# breakout.net
KiCad netlist of a schematic drawn in EAGLE
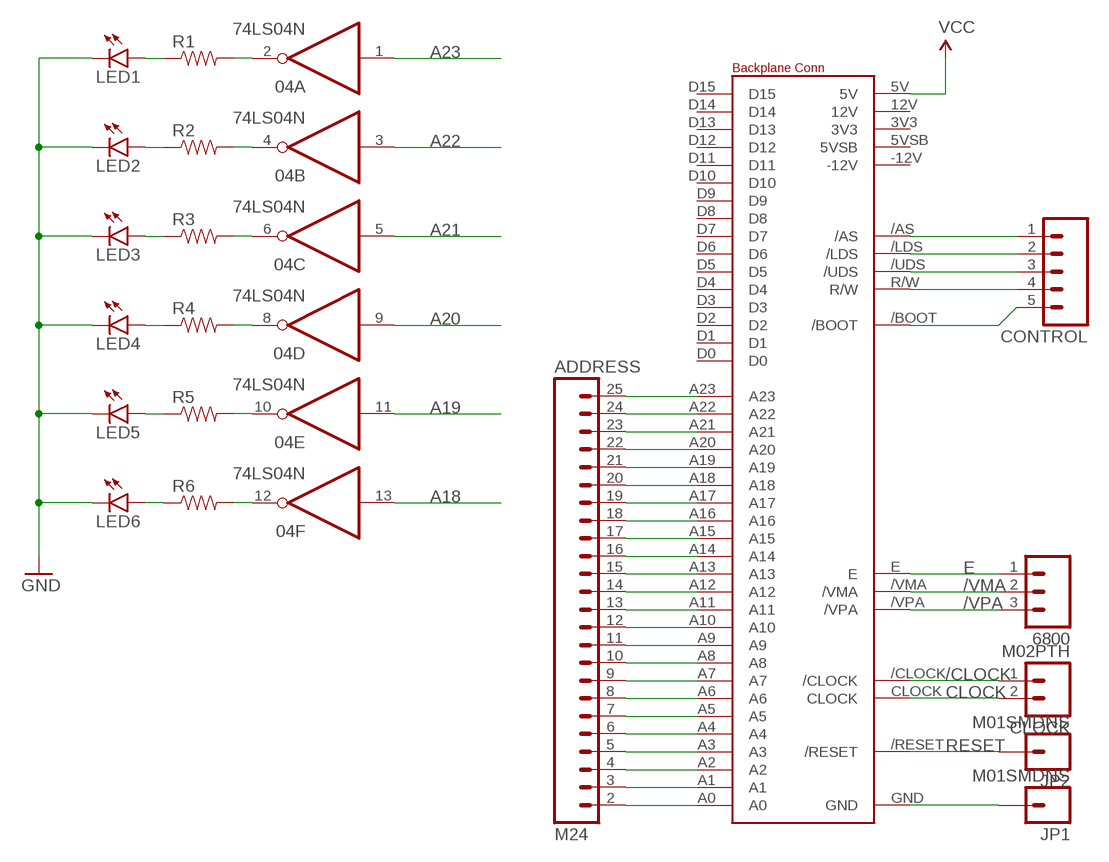
[diagram p0: schematic, sheet 1]

(export (version "E")
  (design (tool "Eeschema 10.0.6"))
  (components
    (comp (ref "04")
      (value "74LS04N")
      (footprint "eagle-import:DIL14")
      (libsource (lib "eagle-import") (part "7404NLS"))
    )
    (comp (ref "6800")
      (value "M03PTH")
      (footprint "eagle-import:1X03")
      (libsource (lib "eagle-import") (part "M03PTH"))
    )
    (comp (ref "ADDRESS")
      (value "M24")
      (footprint "eagle-import:1X24")
      (libsource (lib "eagle-import") (part "M24"))
    )
    (comp (ref "CLOCK")
      (value "M02PTH")
      (footprint "eagle-import:1X02")
      (libsource (lib "eagle-import") (part "M02PTH"))
    )
    (comp (ref "CONTROL")
      (value "M05PTH")
      (footprint "eagle-import:1X05")
      (libsource (lib "eagle-import") (part "M05PTH"))
    )
    (comp (ref "JP1")
      (value "M01SMDNS")
      (footprint "eagle-import:1X01NS")
      (libsource (lib "eagle-import") (part "M01SMDNS"))
    )
    (comp (ref "JP2")
      (value "M01SMDNS")
      (footprint "eagle-import:1X01NS")
      (libsource (lib "eagle-import") (part "M01SMDNS"))
    )
    (comp (ref "LED1")
      (value "LED1206")
      (footprint "eagle-import:LED-1206")
      (libsource (lib "eagle-import") (part "LED1206"))
    )
    (comp (ref "LED2")
      (value "LED1206")
      (footprint "eagle-import:LED-1206")
      (libsource (lib "eagle-import") (part "LED1206"))
    )
    (comp (ref "LED3")
      (value "LED1206")
      (footprint "eagle-import:LED-1206")
      (libsource (lib "eagle-import") (part "LED1206"))
    )
    (comp (ref "LED4")
      (value "LED1206")
      (footprint "eagle-import:LED-1206")
      (libsource (lib "eagle-import") (part "LED1206"))
    )
    (comp (ref "LED5")
      (value "LED1206")
      (footprint "eagle-import:LED-1206")
      (libsource (lib "eagle-import") (part "LED1206"))
    )
    (comp (ref "LED6")
      (value "LED1206")
      (footprint "eagle-import:LED-1206")
      (libsource (lib "eagle-import") (part "LED1206"))
    )
    (comp (ref "R1")
      (value "RESISTOR0603-RES")
      (footprint "eagle-import:0603-RES")
      (libsource (lib "eagle-import") (part "RESISTOR0603-RES"))
    )
    (comp (ref "R2")
      (value "RESISTOR0603-RES")
      (footprint "eagle-import:0603-RES")
      (libsource (lib "eagle-import") (part "RESISTOR0603-RES"))
    )
    (comp (ref "R3")
      (value "RESISTOR0603-RES")
      (footprint "eagle-import:0603-RES")
      (libsource (lib "eagle-import") (part "RESISTOR0603-RES"))
    )
    (comp (ref "R4")
      (value "RESISTOR0603-RES")
      (footprint "eagle-import:0603-RES")
      (libsource (lib "eagle-import") (part "RESISTOR0603-RES"))
    )
    (comp (ref "R5")
      (value "RESISTOR0603-RES")
      (footprint "eagle-import:0603-RES")
      (libsource (lib "eagle-import") (part "RESISTOR0603-RES"))
    )
    (comp (ref "R6")
      (value "RESISTOR0603-RES")
      (footprint "eagle-import:0603-RES")
      (libsource (lib "eagle-import") (part "RESISTOR0603-RES"))
    )
    (comp (ref "U$1")
      (value "BACKPLANENOHOLES")
      (footprint "eagle-import:41612-C")
      (libsource (lib "eagle-import") (part "BACKPLANENOHOLES"))
    )
  )
  (nets
    (net (code "1") (name "/A18") (class "Default")
      (node (ref "04") (pin "13") (pinfunction "I_13") (pintype "input"))
      (node (ref "ADDRESS") (pin "20") (pinfunction "20_20") (pintype "passive"))
      (node (ref "U$1") (pin "A18") (pinfunction "A18_A18") (pintype "bidirectional"))
    )
    (net (code "2") (name "/A19") (class "Default")
      (node (ref "04") (pin "11") (pinfunction "I_11") (pintype "input"))
      (node (ref "ADDRESS") (pin "21") (pinfunction "21_21") (pintype "passive"))
      (node (ref "U$1") (pin "A19") (pinfunction "A19_A19") (pintype "bidirectional"))
    )
    (net (code "3") (name "/A20") (class "Default")
      (node (ref "04") (pin "9") (pinfunction "I_9") (pintype "input"))
      (node (ref "ADDRESS") (pin "22") (pinfunction "22_22") (pintype "passive"))
      (node (ref "U$1") (pin "A20") (pinfunction "A20_A20") (pintype "bidirectional"))
    )
    (net (code "4") (name "/A21") (class "Default")
      (node (ref "04") (pin "5") (pinfunction "I_5") (pintype "input"))
      (node (ref "ADDRESS") (pin "23") (pinfunction "23_23") (pintype "passive"))
      (node (ref "U$1") (pin "A21") (pinfunction "A21_A21") (pintype "bidirectional"))
    )
    (net (code "5") (name "/A22") (class "Default")
      (node (ref "04") (pin "3") (pinfunction "I_3") (pintype "input"))
      (node (ref "ADDRESS") (pin "24") (pinfunction "24_24") (pintype "passive"))
      (node (ref "U$1") (pin "A22") (pinfunction "A22_A22") (pintype "bidirectional"))
    )
    (net (code "6") (name "/A23") (class "Default")
      (node (ref "04") (pin "1") (pinfunction "I_1") (pintype "input"))
      (node (ref "ADDRESS") (pin "25") (pinfunction "25_25") (pintype "passive"))
      (node (ref "U$1") (pin "A23") (pinfunction "A23_A23") (pintype "bidirectional"))
    )
    (net (code "7") (name "/CLOCK") (class "Default")
      (node (ref "CLOCK") (pin "2") (pinfunction "2_2") (pintype "passive"))
      (node (ref "U$1") (pin "CLOCK") (pinfunction "CLOCK_CLOCK") (pintype "bidirectional"))
    )
    (net (code "8") (name "/E") (class "Default")
      (node (ref "6800") (pin "1") (pinfunction "1_1") (pintype "passive"))
      (node (ref "U$1") (pin "E") (pinfunction "E_E") (pintype "bidirectional"))
    )
    (net (code "9") (name "/RESET") (class "Default")
      (node (ref "JP2") (pin "1") (pinfunction "1_1") (pintype "passive"))
      (node (ref "U$1") (pin "/RESET") (pinfunction "/RESET_/RESET") (pintype "bidirectional"))
    )
    (net (code "10") (name "/{slash}CLOCK") (class "Default")
      (node (ref "CLOCK") (pin "1") (pinfunction "1_1") (pintype "passive"))
      (node (ref "U$1") (pin "/CLOCK") (pinfunction "/CLOCK_/CLOCK") (pintype "bidirectional"))
    )
    (net (code "11") (name "/{slash}VMA") (class "Default")
      (node (ref "6800") (pin "2") (pinfunction "2_2") (pintype "passive"))
      (node (ref "U$1") (pin "/VMA") (pinfunction "/VMA_/VMA") (pintype "bidirectional"))
    )
    (net (code "12") (name "/{slash}VPA") (class "Default")
      (node (ref "6800") (pin "3") (pinfunction "3_3") (pintype "passive"))
      (node (ref "U$1") (pin "/VPA") (pinfunction "/VPA_/VPA") (pintype "bidirectional"))
    )
    (net (code "13") (name "GND") (class "Default")
      (node (ref "JP1") (pin "1") (pinfunction "1_1") (pintype "passive"))
      (node (ref "LED1") (pin "C") (pinfunction "C_C") (pintype "passive"))
      (node (ref "LED2") (pin "C") (pinfunction "C_C") (pintype "passive"))
      (node (ref "LED3") (pin "C") (pinfunction "C_C") (pintype "passive"))
      (node (ref "LED4") (pin "C") (pinfunction "C_C") (pintype "passive"))
      (node (ref "LED5") (pin "C") (pinfunction "C_C") (pintype "passive"))
      (node (ref "LED6") (pin "C") (pinfunction "C_C") (pintype "passive"))
      (node (ref "U$1") (pin "GND") (pinfunction "GND_GND") (pintype "bidirectional"))
    )
    (net (code "14") (name "Net-(04A-O)") (class "Default")
      (node (ref "04") (pin "2") (pinfunction "O_2") (pintype "output"))
      (node (ref "R1") (pin "2") (pinfunction "2_2") (pintype "passive"))
    )
    (net (code "15") (name "Net-(04B-O)") (class "Default")
      (node (ref "04") (pin "4") (pinfunction "O_4") (pintype "output"))
      (node (ref "R2") (pin "2") (pinfunction "2_2") (pintype "passive"))
    )
    (net (code "16") (name "Net-(04C-O)") (class "Default")
      (node (ref "04") (pin "6") (pinfunction "O_6") (pintype "output"))
      (node (ref "R3") (pin "2") (pinfunction "2_2") (pintype "passive"))
    )
    (net (code "17") (name "Net-(04D-O)") (class "Default")
      (node (ref "04") (pin "8") (pinfunction "O_8") (pintype "output"))
      (node (ref "R4") (pin "2") (pinfunction "2_2") (pintype "passive"))
    )
    (net (code "18") (name "Net-(04E-O)") (class "Default")
      (node (ref "04") (pin "10") (pinfunction "O_10") (pintype "output"))
      (node (ref "R5") (pin "2") (pinfunction "2_2") (pintype "passive"))
    )
    (net (code "19") (name "Net-(04F-O)") (class "Default")
      (node (ref "04") (pin "12") (pinfunction "O_12") (pintype "output"))
      (node (ref "R6") (pin "2") (pinfunction "2_2") (pintype "passive"))
    )
    (net (code "20") (name "Net-(ADDRESS-Pad2)") (class "Default")
      (node (ref "ADDRESS") (pin "2") (pinfunction "2_2") (pintype "passive"))
      (node (ref "U$1") (pin "A0") (pinfunction "A0_A0") (pintype "bidirectional"))
    )
    (net (code "21") (name "Net-(ADDRESS-Pad3)") (class "Default")
      (node (ref "ADDRESS") (pin "3") (pinfunction "3_3") (pintype "passive"))
      (node (ref "U$1") (pin "A1") (pinfunction "A1_A1") (pintype "bidirectional"))
    )
    (net (code "22") (name "Net-(ADDRESS-Pad4)") (class "Default")
      (node (ref "ADDRESS") (pin "4") (pinfunction "4_4") (pintype "passive"))
      (node (ref "U$1") (pin "A2") (pinfunction "A2_A2") (pintype "bidirectional"))
    )
    (net (code "23") (name "Net-(ADDRESS-Pad5)") (class "Default")
      (node (ref "ADDRESS") (pin "5") (pinfunction "5_5") (pintype "passive"))
      (node (ref "U$1") (pin "A3") (pinfunction "A3_A3") (pintype "bidirectional"))
    )
    (net (code "24") (name "Net-(ADDRESS-Pad6)") (class "Default")
      (node (ref "ADDRESS") (pin "6") (pinfunction "6_6") (pintype "passive"))
      (node (ref "U$1") (pin "A4") (pinfunction "A4_A4") (pintype "bidirectional"))
    )
    (net (code "25") (name "Net-(ADDRESS-Pad7)") (class "Default")
      (node (ref "ADDRESS") (pin "7") (pinfunction "7_7") (pintype "passive"))
      (node (ref "U$1") (pin "A5") (pinfunction "A5_A5") (pintype "bidirectional"))
    )
    (net (code "26") (name "Net-(ADDRESS-Pad8)") (class "Default")
      (node (ref "ADDRESS") (pin "8") (pinfunction "8_8") (pintype "passive"))
      (node (ref "U$1") (pin "A6") (pinfunction "A6_A6") (pintype "bidirectional"))
    )
    (net (code "27") (name "Net-(ADDRESS-Pad9)") (class "Default")
      (node (ref "ADDRESS") (pin "9") (pinfunction "9_9") (pintype "passive"))
      (node (ref "U$1") (pin "A7") (pinfunction "A7_A7") (pintype "bidirectional"))
    )
    (net (code "28") (name "Net-(ADDRESS-Pad10)") (class "Default")
      (node (ref "ADDRESS") (pin "10") (pinfunction "10_10") (pintype "passive"))
      (node (ref "U$1") (pin "A8") (pinfunction "A8_A8") (pintype "bidirectional"))
    )
    (net (code "29") (name "Net-(ADDRESS-Pad11)") (class "Default")
      (node (ref "ADDRESS") (pin "11") (pinfunction "11_11") (pintype "passive"))
      (node (ref "U$1") (pin "A9") (pinfunction "A9_A9") (pintype "bidirectional"))
    )
    (net (code "30") (name "Net-(ADDRESS-Pad12)") (class "Default")
      (node (ref "ADDRESS") (pin "12") (pinfunction "12_12") (pintype "passive"))
      (node (ref "U$1") (pin "A10") (pinfunction "A10_A10") (pintype "bidirectional"))
    )
    (net (code "31") (name "Net-(ADDRESS-Pad13)") (class "Default")
      (node (ref "ADDRESS") (pin "13") (pinfunction "13_13") (pintype "passive"))
      (node (ref "U$1") (pin "A11") (pinfunction "A11_A11") (pintype "bidirectional"))
    )
    (net (code "32") (name "Net-(ADDRESS-Pad14)") (class "Default")
      (node (ref "ADDRESS") (pin "14") (pinfunction "14_14") (pintype "passive"))
      (node (ref "U$1") (pin "A12") (pinfunction "A12_A12") (pintype "bidirectional"))
    )
    (net (code "33") (name "Net-(ADDRESS-Pad15)") (class "Default")
      (node (ref "ADDRESS") (pin "15") (pinfunction "15_15") (pintype "passive"))
      (node (ref "U$1") (pin "A13") (pinfunction "A13_A13") (pintype "bidirectional"))
    )
    (net (code "34") (name "Net-(ADDRESS-Pad16)") (class "Default")
      (node (ref "ADDRESS") (pin "16") (pinfunction "16_16") (pintype "passive"))
      (node (ref "U$1") (pin "A14") (pinfunction "A14_A14") (pintype "bidirectional"))
    )
    (net (code "35") (name "Net-(ADDRESS-Pad17)") (class "Default")
      (node (ref "ADDRESS") (pin "17") (pinfunction "17_17") (pintype "passive"))
      (node (ref "U$1") (pin "A15") (pinfunction "A15_A15") (pintype "bidirectional"))
    )
    (net (code "36") (name "Net-(ADDRESS-Pad18)") (class "Default")
      (node (ref "ADDRESS") (pin "18") (pinfunction "18_18") (pintype "passive"))
      (node (ref "U$1") (pin "A16") (pinfunction "A16_A16") (pintype "bidirectional"))
    )
    (net (code "37") (name "Net-(ADDRESS-Pad19)") (class "Default")
      (node (ref "ADDRESS") (pin "19") (pinfunction "19_19") (pintype "passive"))
      (node (ref "U$1") (pin "A17") (pinfunction "A17_A17") (pintype "bidirectional"))
    )
    (net (code "38") (name "Net-(CONTROL-Pad1)") (class "Default")
      (node (ref "CONTROL") (pin "1") (pinfunction "1_1") (pintype "passive"))
      (node (ref "U$1") (pin "/AS") (pinfunction "/AS_/AS") (pintype "bidirectional"))
    )
    (net (code "39") (name "Net-(CONTROL-Pad2)") (class "Default")
      (node (ref "CONTROL") (pin "2") (pinfunction "2_2") (pintype "passive"))
      (node (ref "U$1") (pin "/LDS") (pinfunction "/LDS_/LDS") (pintype "bidirectional"))
    )
    (net (code "40") (name "Net-(CONTROL-Pad3)") (class "Default")
      (node (ref "CONTROL") (pin "3") (pinfunction "3_3") (pintype "passive"))
      (node (ref "U$1") (pin "/UDS") (pinfunction "/UDS_/UDS") (pintype "bidirectional"))
    )
    (net (code "41") (name "Net-(CONTROL-Pad4)") (class "Default")
      (node (ref "CONTROL") (pin "4") (pinfunction "4_4") (pintype "passive"))
      (node (ref "U$1") (pin "R/W") (pinfunction "R/W_R/W") (pintype "bidirectional"))
    )
    (net (code "42") (name "Net-(CONTROL-Pad5)") (class "Default")
      (node (ref "CONTROL") (pin "5") (pinfunction "5_5") (pintype "passive"))
      (node (ref "U$1") (pin "/BOOT") (pinfunction "/BOOT_/BOOT") (pintype "bidirectional"))
    )
    (net (code "43") (name "Net-(LED1-PadA)") (class "Default")
      (node (ref "LED1") (pin "A") (pinfunction "A_A") (pintype "passive"))
      (node (ref "R1") (pin "1") (pinfunction "1_1") (pintype "passive"))
    )
    (net (code "44") (name "Net-(LED2-PadA)") (class "Default")
      (node (ref "LED2") (pin "A") (pinfunction "A_A") (pintype "passive"))
      (node (ref "R2") (pin "1") (pinfunction "1_1") (pintype "passive"))
    )
    (net (code "45") (name "Net-(LED3-PadA)") (class "Default")
      (node (ref "LED3") (pin "A") (pinfunction "A_A") (pintype "passive"))
      (node (ref "R3") (pin "1") (pinfunction "1_1") (pintype "passive"))
    )
    (net (code "46") (name "Net-(LED4-PadA)") (class "Default")
      (node (ref "LED4") (pin "A") (pinfunction "A_A") (pintype "passive"))
      (node (ref "R4") (pin "1") (pinfunction "1_1") (pintype "passive"))
    )
    (net (code "47") (name "Net-(LED5-PadA)") (class "Default")
      (node (ref "LED5") (pin "A") (pinfunction "A_A") (pintype "passive"))
      (node (ref "R5") (pin "1") (pinfunction "1_1") (pintype "passive"))
    )
    (net (code "48") (name "Net-(LED6-PadA)") (class "Default")
      (node (ref "LED6") (pin "A") (pinfunction "A_A") (pintype "passive"))
      (node (ref "R6") (pin "1") (pinfunction "1_1") (pintype "passive"))
    )
    (net (code "49") (name "VCC") (class "Default")
      (node (ref "U$1") (pin "5V") (pinfunction "5V_5V") (pintype "bidirectional"))
    )
    (net (code "50") (name "unconnected-(U$1-Pad-12V)") (class "Default")
      (node (ref "U$1") (pin "-12V") (pinfunction "-12V_-12V") (pintype "bidirectional"))
    )
    (net (code "51") (name "unconnected-(U$1-Pad3V3)") (class "Default")
      (node (ref "U$1") (pin "3V3") (pinfunction "3V3_3V3") (pintype "bidirectional"))
    )
    (net (code "52") (name "unconnected-(U$1-Pad5VSB)") (class "Default")
      (node (ref "U$1") (pin "5VSB") (pinfunction "5VSB_5VSB") (pintype "bidirectional"))
    )
    (net (code "53") (name "unconnected-(U$1-Pad12V)") (class "Default")
      (node (ref "U$1") (pin "12V") (pinfunction "12V_12V") (pintype "bidirectional"))
    )
    (net (code "54") (name "unconnected-(U$1-PadD0)") (class "Default")
      (node (ref "U$1") (pin "D0") (pinfunction "D0_D0") (pintype "bidirectional"))
    )
    (net (code "55") (name "unconnected-(U$1-PadD1)") (class "Default")
      (node (ref "U$1") (pin "D1") (pinfunction "D1_D1") (pintype "bidirectional"))
    )
    (net (code "56") (name "unconnected-(U$1-PadD2)") (class "Default")
      (node (ref "U$1") (pin "D2") (pinfunction "D2_D2") (pintype "bidirectional"))
    )
    (net (code "57") (name "unconnected-(U$1-PadD3)") (class "Default")
      (node (ref "U$1") (pin "D3") (pinfunction "D3_D3") (pintype "bidirectional"))
    )
    (net (code "58") (name "unconnected-(U$1-PadD4)") (class "Default")
      (node (ref "U$1") (pin "D4") (pinfunction "D4_D4") (pintype "bidirectional"))
    )
    (net (code "59") (name "unconnected-(U$1-PadD5)") (class "Default")
      (node (ref "U$1") (pin "D5") (pinfunction "D5_D5") (pintype "bidirectional"))
    )
    (net (code "60") (name "unconnected-(U$1-PadD6)") (class "Default")
      (node (ref "U$1") (pin "D6") (pinfunction "D6_D6") (pintype "bidirectional"))
    )
    (net (code "61") (name "unconnected-(U$1-PadD7)") (class "Default")
      (node (ref "U$1") (pin "D7") (pinfunction "D7_D7") (pintype "bidirectional"))
    )
    (net (code "62") (name "unconnected-(U$1-PadD8)") (class "Default")
      (node (ref "U$1") (pin "D8") (pinfunction "D8_D8") (pintype "bidirectional"))
    )
    (net (code "63") (name "unconnected-(U$1-PadD9)") (class "Default")
      (node (ref "U$1") (pin "D9") (pinfunction "D9_D9") (pintype "bidirectional"))
    )
    (net (code "64") (name "unconnected-(U$1-PadD10)") (class "Default")
      (node (ref "U$1") (pin "D10") (pinfunction "D10_D10") (pintype "bidirectional"))
    )
    (net (code "65") (name "unconnected-(U$1-PadD11)") (class "Default")
      (node (ref "U$1") (pin "D11") (pinfunction "D11_D11") (pintype "bidirectional"))
    )
    (net (code "66") (name "unconnected-(U$1-PadD12)") (class "Default")
      (node (ref "U$1") (pin "D12") (pinfunction "D12_D12") (pintype "bidirectional"))
    )
    (net (code "67") (name "unconnected-(U$1-PadD13)") (class "Default")
      (node (ref "U$1") (pin "D13") (pinfunction "D13_D13") (pintype "bidirectional"))
    )
    (net (code "68") (name "unconnected-(U$1-PadD14)") (class "Default")
      (node (ref "U$1") (pin "D14") (pinfunction "D14_D14") (pintype "bidirectional"))
    )
    (net (code "69") (name "unconnected-(U$1-PadD15)") (class "Default")
      (node (ref "U$1") (pin "D15") (pinfunction "D15_D15") (pintype "bidirectional"))
    )
  )
)
